# H-Bridge_turning_Sch.net
KiCad netlist of a schematic drawn in Altium Designer
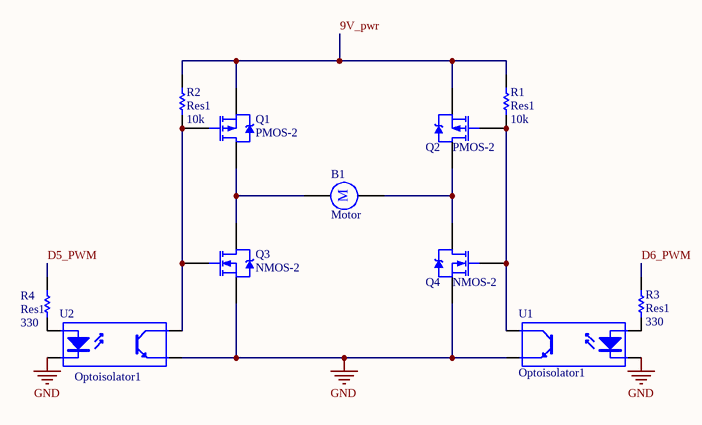
[diagram p0: H-Bridge turning Sch.SchDoc]

(export (version "E")
  (design (tool "Eeschema 10.0.6"))
  (components
    (comp (ref "B1")
      (value "Motor")
      (footprint "HDR1X2")
      (description "Motor, General Kind")
      (fields (field (name "PUBLISHER") "Altium Limited"))
      (libsource (lib "Miscellaneous Devices") (part "Motor"))
    )
    (comp (ref "Q1")
      (value "PMOS-2")
      (footprint "TO-220AB")
      (description "P-Channel Power MOSFET")
      (fields (field (name "PUBLISHER") "Altium Limited"))
      (libsource (lib "Miscellaneous Devices") (part "PMOS-2"))
    )
    (comp (ref "Q2")
      (value "PMOS-2")
      (footprint "TO-220AB")
      (description "P-Channel Power MOSFET")
      (fields (field (name "PUBLISHER") "Altium Limited"))
      (libsource (lib "Miscellaneous Devices") (part "PMOS-2"))
    )
    (comp (ref "Q3")
      (value "NMOS-2")
      (footprint "TO-220AB")
      (description "N-Channel Power MOSFET")
      (fields (field (name "PUBLISHER") "Altium Limited"))
      (libsource (lib "Miscellaneous Devices") (part "NMOS-2"))
    )
    (comp (ref "Q4")
      (value "NMOS-2")
      (footprint "TO-220AB")
      (description "N-Channel Power MOSFET")
      (fields (field (name "PUBLISHER") "Altium Limited"))
      (libsource (lib "Miscellaneous Devices") (part "NMOS-2"))
    )
    (comp (ref "R1")
      (value "Res1")
      (footprint "6-0805_N")
      (description "Resistor")
      (fields (field (name "ALTIUM_VALUE") "10k") (field (name "PUBLISHER") "Altium Limited"))
      (libsource (lib "Miscellaneous Devices") (part "Res1"))
    )
    (comp (ref "R2")
      (value "Res1")
      (footprint "6-0805_N")
      (description "Resistor")
      (fields (field (name "ALTIUM_VALUE") "10k") (field (name "PUBLISHER") "Altium Limited"))
      (libsource (lib "Miscellaneous Devices") (part "Res1"))
    )
    (comp (ref "R3")
      (value "Res1")
      (footprint "6-0805_N")
      (description "Resistor")
      (fields (field (name "ALTIUM_VALUE") "330") (field (name "PUBLISHER") "Altium Limited"))
      (libsource (lib "Miscellaneous Devices") (part "Res1"))
    )
    (comp (ref "R4")
      (value "Res1")
      (footprint "6-0805_N")
      (description "Resistor")
      (fields (field (name "ALTIUM_VALUE") "330") (field (name "PUBLISHER") "Altium Limited"))
      (libsource (lib "Miscellaneous Devices") (part "Res1"))
    )
    (comp (ref "U1")
      (value "Optoisolator1")
      (footprint "DIP-4")
      (description "4-Pin Phototransistor Optocoupler")
      (fields (field (name "PUBLISHER") "Altium Limited"))
      (libsource (lib "Miscellaneous Devices") (part "Optoisolator1"))
    )
    (comp (ref "U2")
      (value "Optoisolator1")
      (footprint "DIP-4")
      (description "4-Pin Phototransistor Optocoupler")
      (fields (field (name "PUBLISHER") "Altium Limited"))
      (libsource (lib "Miscellaneous Devices") (part "Optoisolator1"))
    )
  )
  (nets
    (net (code "1") (name "/9V_pwr") (class "Default")
      (node (ref "Q1") (pin "3") (pinfunction "S_3") (pintype "passive"))
      (node (ref "Q2") (pin "3") (pinfunction "S_3") (pintype "passive"))
      (node (ref "R1") (pin "2") (pinfunction "2_2") (pintype "passive"))
      (node (ref "R2") (pin "2") (pinfunction "2_2") (pintype "passive"))
    )
    (net (code "2") (name "/D5_PWM") (class "Default")
      (node (ref "R4") (pin "2") (pinfunction "2_2") (pintype "passive"))
    )
    (net (code "3") (name "/D6_PWM") (class "Default")
      (node (ref "R3") (pin "2") (pinfunction "2_2") (pintype "passive"))
    )
    (net (code "4") (name "GND") (class "Default")
      (node (ref "Q3") (pin "3") (pinfunction "S_3") (pintype "passive"))
      (node (ref "Q4") (pin "3") (pinfunction "S_3") (pintype "passive"))
      (node (ref "U1") (pin "2") (pinfunction "K_2") (pintype "passive"))
      (node (ref "U1") (pin "3") (pinfunction "E_3") (pintype "passive"))
      (node (ref "U2") (pin "2") (pinfunction "K_2") (pintype "passive"))
      (node (ref "U2") (pin "3") (pinfunction "E_3") (pintype "passive"))
    )
    (net (code "5") (name "Net-(Q1-D)") (class "Default")
      (node (ref "B1") (pin "1") (pinfunction "1_1") (pintype "passive"))
      (node (ref "Q1") (pin "2") (pinfunction "D_2") (pintype "passive"))
      (node (ref "Q3") (pin "2") (pinfunction "D_2") (pintype "passive"))
    )
    (net (code "6") (name "Net-(Q1-G)") (class "Default")
      (node (ref "Q1") (pin "1") (pinfunction "G_1") (pintype "passive"))
      (node (ref "Q3") (pin "1") (pinfunction "G_1") (pintype "passive"))
      (node (ref "R2") (pin "1") (pinfunction "1_1") (pintype "passive"))
      (node (ref "U2") (pin "4") (pinfunction "C_4") (pintype "passive"))
    )
    (net (code "7") (name "Net-(Q2-D)") (class "Default")
      (node (ref "B1") (pin "2") (pinfunction "2_2") (pintype "passive"))
      (node (ref "Q2") (pin "2") (pinfunction "D_2") (pintype "passive"))
      (node (ref "Q4") (pin "2") (pinfunction "D_2") (pintype "passive"))
    )
    (net (code "8") (name "Net-(Q2-G)") (class "Default")
      (node (ref "Q2") (pin "1") (pinfunction "G_1") (pintype "passive"))
      (node (ref "Q4") (pin "1") (pinfunction "G_1") (pintype "passive"))
      (node (ref "R1") (pin "1") (pinfunction "1_1") (pintype "passive"))
      (node (ref "U1") (pin "4") (pinfunction "C_4") (pintype "passive"))
    )
    (net (code "9") (name "Net-(U1-A)") (class "Default")
      (node (ref "R3") (pin "1") (pinfunction "1_1") (pintype "passive"))
      (node (ref "U1") (pin "1") (pinfunction "A_1") (pintype "passive"))
    )
    (net (code "10") (name "Net-(U2-A)") (class "Default")
      (node (ref "R4") (pin "1") (pinfunction "1_1") (pintype "passive"))
      (node (ref "U2") (pin "1") (pinfunction "A_1") (pintype "passive"))
    )
  )
)
